# TinyNES_RGB_DIN_Cable.net
KiCad netlist of a schematic drawn in EAGLE
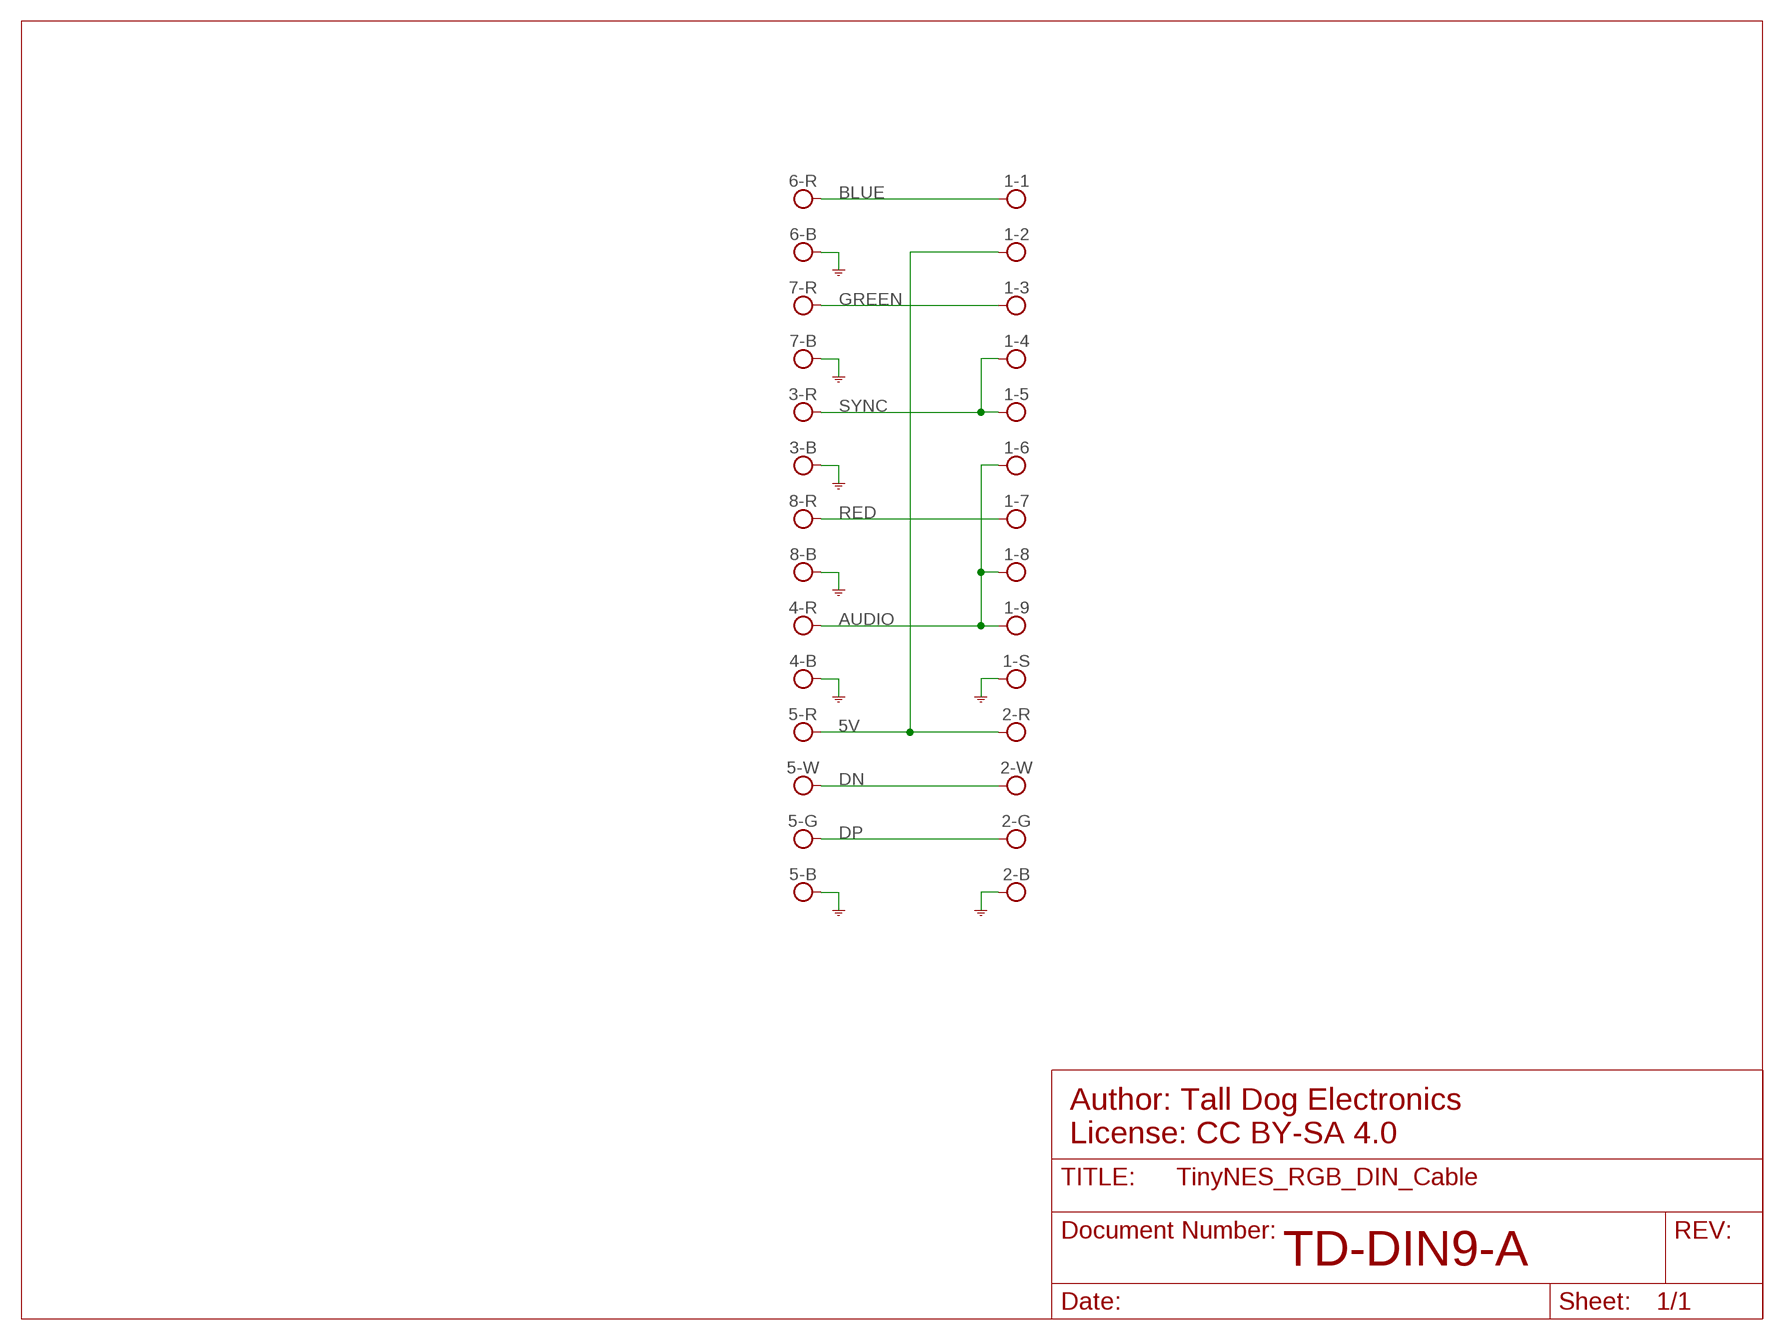
[diagram p0: schematic, sheet 1]

(export (version "E")
  (design (tool "Eeschema 10.0.6"))
  (components
    (comp (ref "1-1")
      (value "HOLE-CABLE-PAD")
      (footprint "eagle-import:CABLE-PAD")
      (libsource (lib "eagle-import") (part "HOLE-CABLE-PAD"))
    )
    (comp (ref "1-2")
      (value "HOLE-CABLE-PAD")
      (footprint "eagle-import:CABLE-PAD")
      (libsource (lib "eagle-import") (part "HOLE-CABLE-PAD"))
    )
    (comp (ref "1-3")
      (value "HOLE-CABLE-PAD")
      (footprint "eagle-import:CABLE-PAD")
      (libsource (lib "eagle-import") (part "HOLE-CABLE-PAD"))
    )
    (comp (ref "1-4")
      (value "HOLE-CABLE-PAD")
      (footprint "eagle-import:CABLE-PAD")
      (libsource (lib "eagle-import") (part "HOLE-CABLE-PAD"))
    )
    (comp (ref "1-5")
      (value "HOLE-CABLE-PAD")
      (footprint "eagle-import:CABLE-PAD")
      (libsource (lib "eagle-import") (part "HOLE-CABLE-PAD"))
    )
    (comp (ref "1-6")
      (value "HOLE-CABLE-PAD")
      (footprint "eagle-import:CABLE-PAD")
      (libsource (lib "eagle-import") (part "HOLE-CABLE-PAD"))
    )
    (comp (ref "1-7")
      (value "HOLE-CABLE-PAD")
      (footprint "eagle-import:CABLE-PAD")
      (libsource (lib "eagle-import") (part "HOLE-CABLE-PAD"))
    )
    (comp (ref "1-8")
      (value "HOLE-CABLE-PAD")
      (footprint "eagle-import:CABLE-PAD")
      (libsource (lib "eagle-import") (part "HOLE-CABLE-PAD"))
    )
    (comp (ref "1-9")
      (value "HOLE-CABLE-PAD")
      (footprint "eagle-import:CABLE-PAD")
      (libsource (lib "eagle-import") (part "HOLE-CABLE-PAD"))
    )
    (comp (ref "1-S")
      (value "HOLE-CABLE-PAD")
      (footprint "eagle-import:CABLE-PAD")
      (libsource (lib "eagle-import") (part "HOLE-CABLE-PAD"))
    )
    (comp (ref "2-B")
      (value "HOLE-CABLE-PAD")
      (footprint "eagle-import:CABLE-PAD")
      (libsource (lib "eagle-import") (part "HOLE-CABLE-PAD"))
    )
    (comp (ref "2-G")
      (value "HOLE-CABLE-PAD")
      (footprint "eagle-import:CABLE-PAD")
      (libsource (lib "eagle-import") (part "HOLE-CABLE-PAD"))
    )
    (comp (ref "2-R")
      (value "HOLE-CABLE-PAD")
      (footprint "eagle-import:CABLE-PAD")
      (libsource (lib "eagle-import") (part "HOLE-CABLE-PAD"))
    )
    (comp (ref "2-W")
      (value "HOLE-CABLE-PAD")
      (footprint "eagle-import:CABLE-PAD")
      (libsource (lib "eagle-import") (part "HOLE-CABLE-PAD"))
    )
    (comp (ref "3-B")
      (value "HOLE-CABLE-PAD")
      (footprint "eagle-import:CABLE-PAD")
      (libsource (lib "eagle-import") (part "HOLE-CABLE-PAD"))
    )
    (comp (ref "3-R")
      (value "HOLE-CABLE-PAD")
      (footprint "eagle-import:CABLE-PAD")
      (libsource (lib "eagle-import") (part "HOLE-CABLE-PAD"))
    )
    (comp (ref "4-B")
      (value "HOLE-CABLE-PAD")
      (footprint "eagle-import:CABLE-PAD")
      (libsource (lib "eagle-import") (part "HOLE-CABLE-PAD"))
    )
    (comp (ref "4-R")
      (value "HOLE-CABLE-PAD")
      (footprint "eagle-import:CABLE-PAD")
      (libsource (lib "eagle-import") (part "HOLE-CABLE-PAD"))
    )
    (comp (ref "5-B")
      (value "HOLE-CABLE-PAD")
      (footprint "eagle-import:CABLE-PAD")
      (libsource (lib "eagle-import") (part "HOLE-CABLE-PAD"))
    )
    (comp (ref "5-G")
      (value "HOLE-CABLE-PAD")
      (footprint "eagle-import:CABLE-PAD")
      (libsource (lib "eagle-import") (part "HOLE-CABLE-PAD"))
    )
    (comp (ref "5-R")
      (value "HOLE-CABLE-PAD")
      (footprint "eagle-import:CABLE-PAD")
      (libsource (lib "eagle-import") (part "HOLE-CABLE-PAD"))
    )
    (comp (ref "5-W")
      (value "HOLE-CABLE-PAD")
      (footprint "eagle-import:CABLE-PAD")
      (libsource (lib "eagle-import") (part "HOLE-CABLE-PAD"))
    )
    (comp (ref "6-B")
      (value "HOLE-CABLE-PAD")
      (footprint "eagle-import:CABLE-PAD")
      (libsource (lib "eagle-import") (part "HOLE-CABLE-PAD"))
    )
    (comp (ref "6-R")
      (value "HOLE-CABLE-PAD")
      (footprint "eagle-import:CABLE-PAD")
      (libsource (lib "eagle-import") (part "HOLE-CABLE-PAD"))
    )
    (comp (ref "7-B")
      (value "HOLE-CABLE-PAD")
      (footprint "eagle-import:CABLE-PAD")
      (libsource (lib "eagle-import") (part "HOLE-CABLE-PAD"))
    )
    (comp (ref "7-R")
      (value "HOLE-CABLE-PAD")
      (footprint "eagle-import:CABLE-PAD")
      (libsource (lib "eagle-import") (part "HOLE-CABLE-PAD"))
    )
    (comp (ref "8-B")
      (value "HOLE-CABLE-PAD")
      (footprint "eagle-import:CABLE-PAD")
      (libsource (lib "eagle-import") (part "HOLE-CABLE-PAD"))
    )
    (comp (ref "8-R")
      (value "HOLE-CABLE-PAD")
      (footprint "eagle-import:CABLE-PAD")
      (libsource (lib "eagle-import") (part "HOLE-CABLE-PAD"))
    )
  )
  (nets
    (net (code "1") (name "/5V") (class "Default")
      (node (ref "1-2") (pin "P") (pinfunction "P$1_P") (pintype "bidirectional"))
      (node (ref "2-R") (pin "P") (pinfunction "P$1_P") (pintype "bidirectional"))
      (node (ref "5-R") (pin "P") (pinfunction "P$1_P") (pintype "bidirectional"))
    )
    (net (code "2") (name "/AUDIO") (class "Default")
      (node (ref "1-6") (pin "P") (pinfunction "P$1_P") (pintype "bidirectional"))
      (node (ref "1-8") (pin "P") (pinfunction "P$1_P") (pintype "bidirectional"))
      (node (ref "1-9") (pin "P") (pinfunction "P$1_P") (pintype "bidirectional"))
      (node (ref "4-R") (pin "P") (pinfunction "P$1_P") (pintype "bidirectional"))
    )
    (net (code "3") (name "/BLUE") (class "Default")
      (node (ref "1-1") (pin "P") (pinfunction "P$1_P") (pintype "bidirectional"))
      (node (ref "6-R") (pin "P") (pinfunction "P$1_P") (pintype "bidirectional"))
    )
    (net (code "4") (name "/DN") (class "Default")
      (node (ref "2-W") (pin "P") (pinfunction "P$1_P") (pintype "bidirectional"))
      (node (ref "5-W") (pin "P") (pinfunction "P$1_P") (pintype "bidirectional"))
    )
    (net (code "5") (name "/DP") (class "Default")
      (node (ref "2-G") (pin "P") (pinfunction "P$1_P") (pintype "bidirectional"))
      (node (ref "5-G") (pin "P") (pinfunction "P$1_P") (pintype "bidirectional"))
    )
    (net (code "6") (name "/GREEN") (class "Default")
      (node (ref "1-3") (pin "P") (pinfunction "P$1_P") (pintype "bidirectional"))
      (node (ref "7-R") (pin "P") (pinfunction "P$1_P") (pintype "bidirectional"))
    )
    (net (code "7") (name "/RED") (class "Default")
      (node (ref "1-7") (pin "P") (pinfunction "P$1_P") (pintype "bidirectional"))
      (node (ref "8-R") (pin "P") (pinfunction "P$1_P") (pintype "bidirectional"))
    )
    (net (code "8") (name "/SYNC") (class "Default")
      (node (ref "1-4") (pin "P") (pinfunction "P$1_P") (pintype "bidirectional"))
      (node (ref "1-5") (pin "P") (pinfunction "P$1_P") (pintype "bidirectional"))
      (node (ref "3-R") (pin "P") (pinfunction "P$1_P") (pintype "bidirectional"))
    )
    (net (code "9") (name "GND") (class "Default")
      (node (ref "1-S") (pin "P") (pinfunction "P$1_P") (pintype "bidirectional"))
      (node (ref "2-B") (pin "P") (pinfunction "P$1_P") (pintype "bidirectional"))
      (node (ref "3-B") (pin "P") (pinfunction "P$1_P") (pintype "bidirectional"))
      (node (ref "4-B") (pin "P") (pinfunction "P$1_P") (pintype "bidirectional"))
      (node (ref "5-B") (pin "P") (pinfunction "P$1_P") (pintype "bidirectional"))
      (node (ref "6-B") (pin "P") (pinfunction "P$1_P") (pintype "bidirectional"))
      (node (ref "7-B") (pin "P") (pinfunction "P$1_P") (pintype "bidirectional"))
      (node (ref "8-B") (pin "P") (pinfunction "P$1_P") (pintype "bidirectional"))
    )
  )
)
